# T_STorM32_motor_v24E-molex.net
KiCad netlist of a schematic drawn in EAGLE
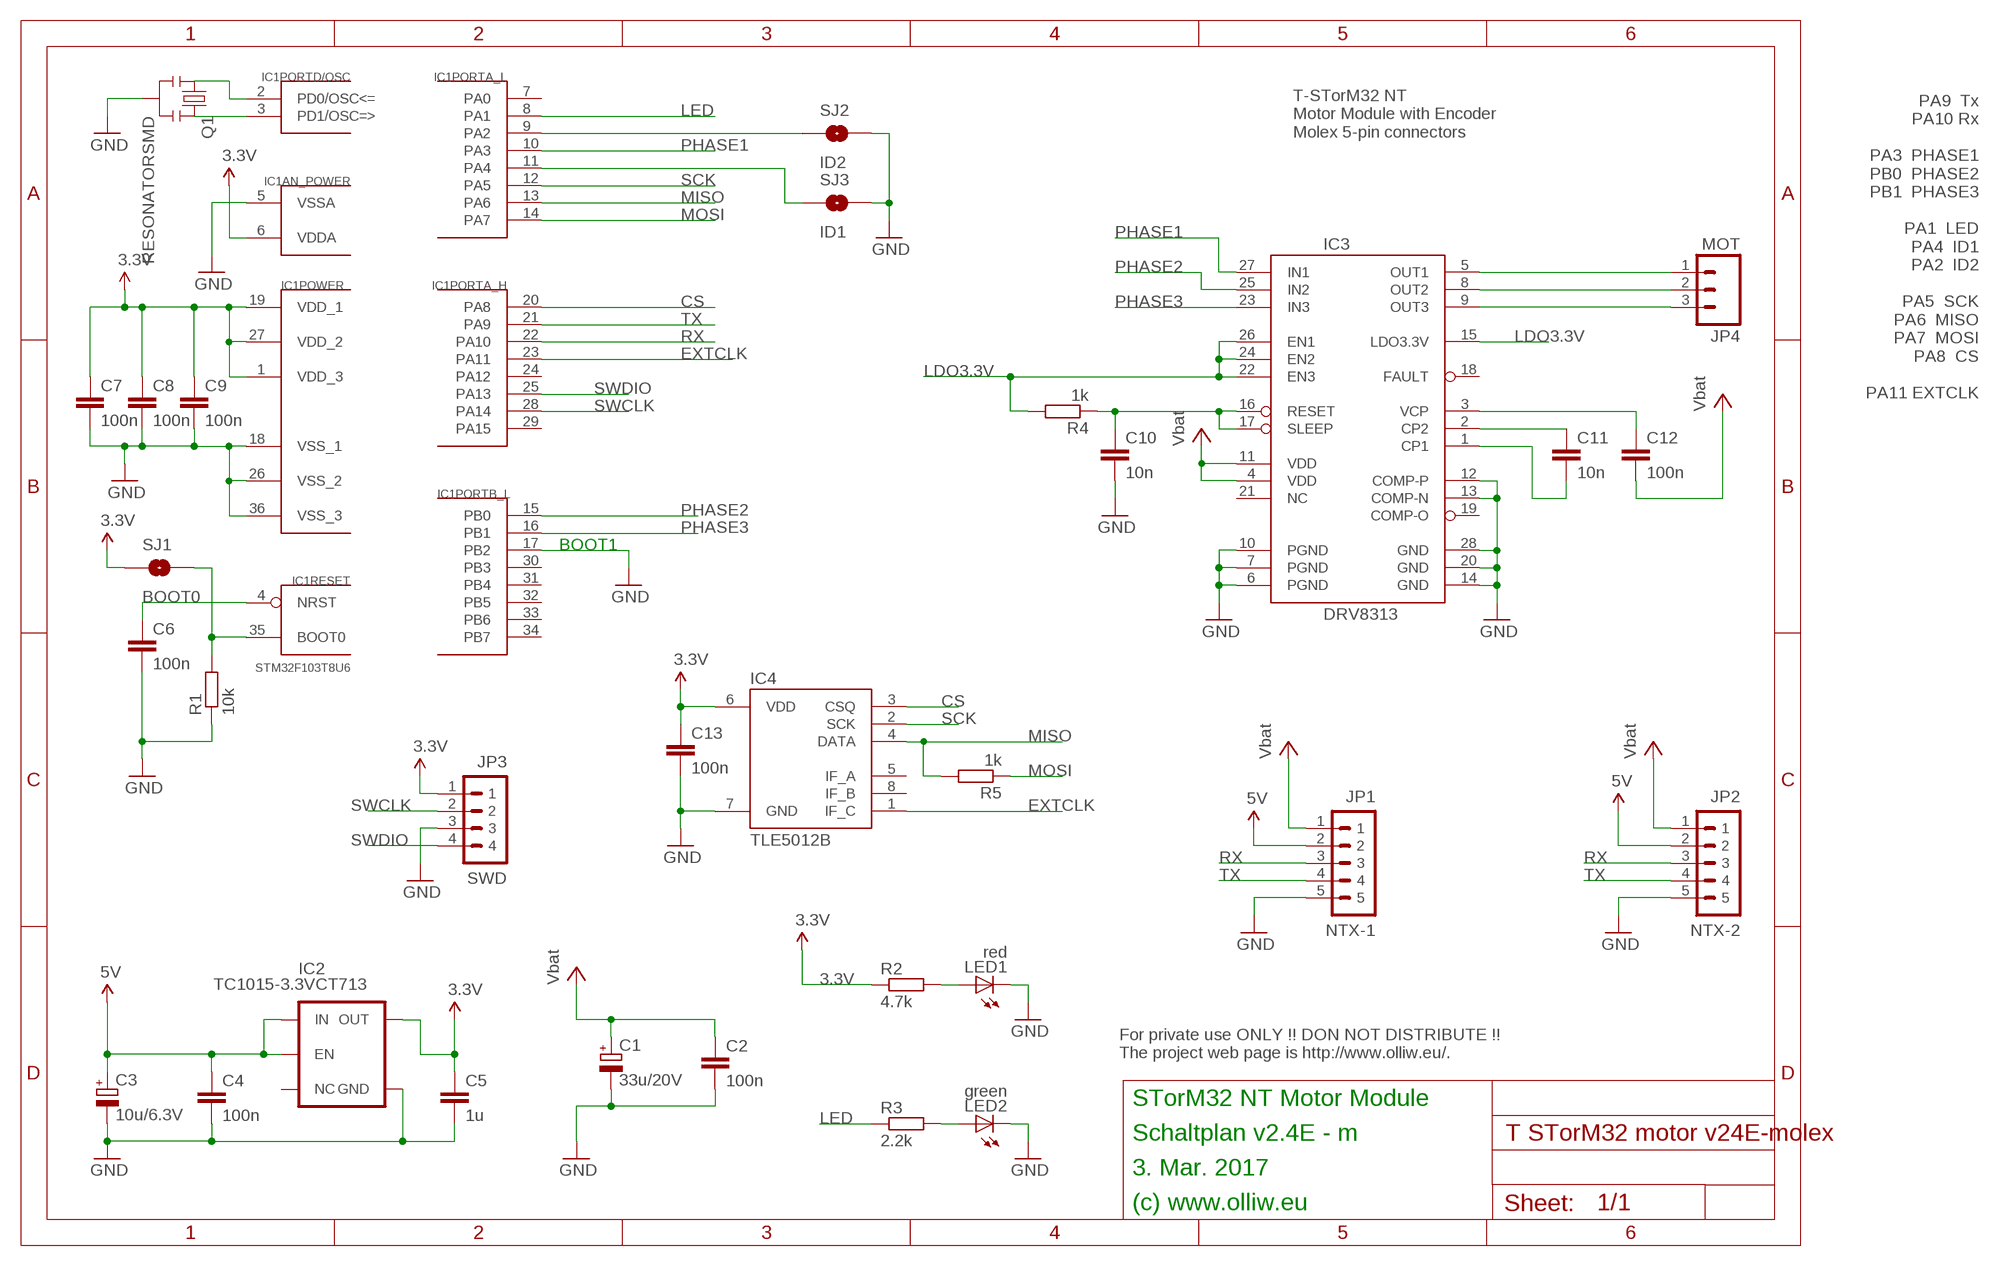
[diagram p0: schematic, sheet 1]

(export (version "E")
  (design (tool "Eeschema 10.0.6"))
  (components
    (comp (ref "C1")
      (value "33u/20V")
      (footprint "eagle-import:SMC_C")
      (libsource (lib "eagle-import") (part "CPOL-EUSMCC"))
    )
    (comp (ref "C2")
      (value "100n")
      (footprint "eagle-import:C0603")
      (libsource (lib "eagle-import") (part "C-EUC0603"))
    )
    (comp (ref "C3")
      (value "10u/6.3V")
      (footprint "eagle-import:SMC_B")
      (libsource (lib "eagle-import") (part "CPOL-EUSMCB"))
    )
    (comp (ref "C4")
      (value "100n")
      (footprint "eagle-import:C0603")
      (libsource (lib "eagle-import") (part "C-EUC0603"))
    )
    (comp (ref "C5")
      (value "1u")
      (footprint "eagle-import:C0603")
      (libsource (lib "eagle-import") (part "C-EUC0603"))
    )
    (comp (ref "C6")
      (value "100n")
      (footprint "eagle-import:C0603")
      (libsource (lib "eagle-import") (part "C-EUC0603"))
    )
    (comp (ref "C7")
      (value "100n")
      (footprint "eagle-import:C0603")
      (libsource (lib "eagle-import") (part "C-EUC0603"))
    )
    (comp (ref "C8")
      (value "100n")
      (footprint "eagle-import:C0603")
      (libsource (lib "eagle-import") (part "C-EUC0603"))
    )
    (comp (ref "C9")
      (value "100n")
      (footprint "eagle-import:C0603")
      (libsource (lib "eagle-import") (part "C-EUC0603"))
    )
    (comp (ref "C10")
      (value "10n")
      (footprint "eagle-import:C0603")
      (libsource (lib "eagle-import") (part "C-EUC0603"))
    )
    (comp (ref "C11")
      (value "10n")
      (footprint "eagle-import:C0603")
      (libsource (lib "eagle-import") (part "C-EUC0603"))
    )
    (comp (ref "C12")
      (value "100n")
      (footprint "eagle-import:C0603")
      (libsource (lib "eagle-import") (part "C-EUC0603"))
    )
    (comp (ref "C13")
      (value "100n")
      (footprint "eagle-import:C0603")
      (libsource (lib "eagle-import") (part "C-EUC0603"))
    )
    (comp (ref "IC1")
      (value "STM32F103T8U6")
      (footprint "eagle-import:VFQFPN36")
      (libsource (lib "eagle-import") (part "STM32F10XTXU6"))
    )
    (comp (ref "IC2")
      (value "TC1015-3.3VCT713")
      (footprint "eagle-import:SOT23-5")
      (libsource (lib "eagle-import") (part "V_REG_TPS76433SOT23-5"))
    )
    (comp (ref "IC3")
      (value "DRV8313")
      (footprint "eagle-import:HTSSOP28")
      (libsource (lib "eagle-import") (part "DRV8313"))
    )
    (comp (ref "IC4")
      (value "TLE5012B")
      (footprint "eagle-import:SO08")
      (libsource (lib "eagle-import") (part "TLE5012B"))
    )
    (comp (ref "JP1")
      (value "NTX-1")
      (footprint "eagle-import:MOLEX-53261-05-SMD-FLAT")
      (libsource (lib "eagle-import") (part "P5X1_1P27"))
    )
    (comp (ref "JP2")
      (value "NTX-2")
      (footprint "eagle-import:MOLEX-53261-05-SMD-FLAT")
      (libsource (lib "eagle-import") (part "P5X1_1P27"))
    )
    (comp (ref "JP3")
      (value "SWD")
      (footprint "eagle-import:4X1_1P27_OCT_BILEX")
      (libsource (lib "eagle-import") (part "P4X1_1P27-OCT_BILEX"))
    )
    (comp (ref "JP4")
      (value "MOT")
      (footprint "eagle-import:1X03")
      (libsource (lib "eagle-import") (part "M03PTH"))
    )
    (comp (ref "LED1")
      (value "red")
      (footprint "eagle-import:CHIPLED_0603")
      (libsource (lib "eagle-import") (part "LEDCHIPLED_0603"))
    )
    (comp (ref "LED2")
      (value "green")
      (footprint "eagle-import:CHIPLED_0603")
      (libsource (lib "eagle-import") (part "LEDCHIPLED_0603"))
    )
    (comp (ref "Q1")
      (value "RESONATORSMD")
      (footprint "eagle-import:RESONATOR-SMD")
      (libsource (lib "eagle-import") (part "RESONATORSMD"))
    )
    (comp (ref "R1")
      (value "10k")
      (footprint "eagle-import:R0603")
      (libsource (lib "eagle-import") (part "R-EU_R0603"))
    )
    (comp (ref "R2")
      (value "4.7k")
      (footprint "eagle-import:R0603")
      (libsource (lib "eagle-import") (part "R-EU_R0603"))
    )
    (comp (ref "R3")
      (value "2.2k")
      (footprint "eagle-import:R0603")
      (libsource (lib "eagle-import") (part "R-EU_R0603"))
    )
    (comp (ref "R4")
      (value "1k")
      (footprint "eagle-import:R0603")
      (libsource (lib "eagle-import") (part "R-EU_R0603"))
    )
    (comp (ref "R5")
      (value "1k")
      (footprint "eagle-import:R0603")
      (libsource (lib "eagle-import") (part "R-EU_R0603"))
    )
    (comp (ref "SJ1")
      (value "BOOT0")
      (footprint "eagle-import:SJ_2S-NO")
      (libsource (lib "eagle-import") (part "SOLDERJUMPERNO"))
    )
    (comp (ref "SJ2")
      (value "ID2")
      (footprint "eagle-import:SJ_2S-NO")
      (libsource (lib "eagle-import") (part "SOLDERJUMPERNO"))
    )
    (comp (ref "SJ3")
      (value "ID1")
      (footprint "eagle-import:SJ_2S-NO")
      (libsource (lib "eagle-import") (part "SOLDERJUMPERNO"))
    )
  )
  (nets
    (net (code "1") (name "/CS") (class "Default")
      (node (ref "IC1") (pin "20") (pinfunction "PA8_20") (pintype "bidirectional"))
      (node (ref "IC4") (pin "3") (pinfunction "CSQ_3") (pintype "input"))
    )
    (net (code "2") (name "/EXTCLK") (class "Default")
      (node (ref "IC1") (pin "23") (pinfunction "PA11_23") (pintype "bidirectional"))
      (node (ref "IC4") (pin "1") (pinfunction "IF_C_1") (pintype "bidirectional"))
    )
    (net (code "3") (name "/LDO3.3V") (class "Default")
      (node (ref "IC3") (pin "15") (pinfunction "LDO3.3V_15") (pintype "output"))
      (node (ref "IC3") (pin "22") (pinfunction "EN3_22") (pintype "input"))
      (node (ref "IC3") (pin "24") (pinfunction "EN2_24") (pintype "input"))
      (node (ref "IC3") (pin "26") (pinfunction "EN1_26") (pintype "input"))
      (node (ref "R4") (pin "2") (pinfunction "2_2") (pintype "passive"))
    )
    (net (code "4") (name "/LED") (class "Default")
      (node (ref "IC1") (pin "8") (pinfunction "PA1_8") (pintype "bidirectional"))
      (node (ref "R3") (pin "1") (pinfunction "1_1") (pintype "passive"))
    )
    (net (code "5") (name "/MISO") (class "Default")
      (node (ref "IC1") (pin "13") (pinfunction "PA6_13") (pintype "bidirectional"))
      (node (ref "IC4") (pin "4") (pinfunction "DATA_4") (pintype "bidirectional"))
      (node (ref "R5") (pin "2") (pinfunction "2_2") (pintype "passive"))
    )
    (net (code "6") (name "/MOSI") (class "Default")
      (node (ref "IC1") (pin "14") (pinfunction "PA7_14") (pintype "bidirectional"))
      (node (ref "R5") (pin "1") (pinfunction "1_1") (pintype "passive"))
    )
    (net (code "7") (name "/PHASE1") (class "Default")
      (node (ref "IC1") (pin "10") (pinfunction "PA3_10") (pintype "bidirectional"))
      (node (ref "IC3") (pin "27") (pinfunction "IN1_27") (pintype "input"))
    )
    (net (code "8") (name "/PHASE2") (class "Default")
      (node (ref "IC1") (pin "15") (pinfunction "PB0_15") (pintype "bidirectional"))
      (node (ref "IC3") (pin "25") (pinfunction "IN2_25") (pintype "input"))
    )
    (net (code "9") (name "/PHASE3") (class "Default")
      (node (ref "IC1") (pin "16") (pinfunction "PB1_16") (pintype "bidirectional"))
      (node (ref "IC3") (pin "23") (pinfunction "IN3_23") (pintype "input"))
    )
    (net (code "10") (name "/RX") (class "Default")
      (node (ref "IC1") (pin "22") (pinfunction "PA10_22") (pintype "bidirectional"))
      (node (ref "JP1") (pin "3") (pinfunction "3_3") (pintype "passive"))
      (node (ref "JP2") (pin "3") (pinfunction "3_3") (pintype "passive"))
    )
    (net (code "11") (name "/SCK") (class "Default")
      (node (ref "IC1") (pin "12") (pinfunction "PA5_12") (pintype "bidirectional"))
      (node (ref "IC4") (pin "2") (pinfunction "SCK_2") (pintype "input"))
    )
    (net (code "12") (name "/SWCLK") (class "Default")
      (node (ref "IC1") (pin "28") (pinfunction "PA14_28") (pintype "bidirectional"))
      (node (ref "JP3") (pin "2") (pinfunction "2_2") (pintype "passive"))
    )
    (net (code "13") (name "/SWDIO") (class "Default")
      (node (ref "IC1") (pin "25") (pinfunction "PA13_25") (pintype "bidirectional"))
      (node (ref "JP3") (pin "4") (pinfunction "4_4") (pintype "passive"))
    )
    (net (code "14") (name "/TX") (class "Default")
      (node (ref "IC1") (pin "21") (pinfunction "PA9_21") (pintype "bidirectional"))
      (node (ref "JP1") (pin "4") (pinfunction "4_4") (pintype "passive"))
      (node (ref "JP2") (pin "4") (pinfunction "4_4") (pintype "passive"))
    )
    (net (code "15") (name "3.3V") (class "Default")
      (node (ref "C13") (pin "1") (pinfunction "1_1") (pintype "passive"))
      (node (ref "C5") (pin "1") (pinfunction "1_1") (pintype "passive"))
      (node (ref "C7") (pin "1") (pinfunction "1_1") (pintype "passive"))
      (node (ref "C8") (pin "1") (pinfunction "1_1") (pintype "passive"))
      (node (ref "C9") (pin "1") (pinfunction "1_1") (pintype "passive"))
      (node (ref "IC1") (pin "1") (pinfunction "VDD_3_1") (pintype "power_in"))
      (node (ref "IC1") (pin "19") (pinfunction "VDD_1_19") (pintype "power_in"))
      (node (ref "IC1") (pin "27") (pinfunction "VDD_2_27") (pintype "power_in"))
      (node (ref "IC1") (pin "6") (pinfunction "VDDA_6") (pintype "power_in"))
      (node (ref "IC2") (pin "5") (pinfunction "OUT_5") (pintype "passive"))
      (node (ref "IC4") (pin "6") (pinfunction "VDD_6") (pintype "power_in"))
      (node (ref "JP3") (pin "1") (pinfunction "1_1") (pintype "passive"))
      (node (ref "R2") (pin "1") (pinfunction "1_1") (pintype "passive"))
      (node (ref "SJ1") (pin "1") (pinfunction "1_1") (pintype "passive"))
    )
    (net (code "16") (name "5V") (class "Default")
      (node (ref "C3") (pin "+") (pinfunction "+_+") (pintype "passive"))
      (node (ref "C4") (pin "1") (pinfunction "1_1") (pintype "passive"))
      (node (ref "IC2") (pin "1") (pinfunction "IN_1") (pintype "input"))
      (node (ref "IC2") (pin "3") (pinfunction "EN_3") (pintype "input"))
      (node (ref "JP1") (pin "2") (pinfunction "2_2") (pintype "passive"))
      (node (ref "JP2") (pin "2") (pinfunction "2_2") (pintype "passive"))
    )
    (net (code "17") (name "GND") (class "Default")
      (node (ref "C1") (pin "-") (pinfunction "-_-") (pintype "passive"))
      (node (ref "C10") (pin "2") (pinfunction "2_2") (pintype "passive"))
      (node (ref "C13") (pin "2") (pinfunction "2_2") (pintype "passive"))
      (node (ref "C2") (pin "2") (pinfunction "2_2") (pintype "passive"))
      (node (ref "C3") (pin "-") (pinfunction "-_-") (pintype "passive"))
      (node (ref "C4") (pin "2") (pinfunction "2_2") (pintype "passive"))
      (node (ref "C5") (pin "2") (pinfunction "2_2") (pintype "passive"))
      (node (ref "C6") (pin "2") (pinfunction "2_2") (pintype "passive"))
      (node (ref "C7") (pin "2") (pinfunction "2_2") (pintype "passive"))
      (node (ref "C8") (pin "2") (pinfunction "2_2") (pintype "passive"))
      (node (ref "C9") (pin "2") (pinfunction "2_2") (pintype "passive"))
      (node (ref "IC1") (pin "17") (pinfunction "PB2_17") (pintype "bidirectional"))
      (node (ref "IC1") (pin "18") (pinfunction "VSS_1_18") (pintype "power_in"))
      (node (ref "IC1") (pin "26") (pinfunction "VSS_2_26") (pintype "power_in"))
      (node (ref "IC1") (pin "36") (pinfunction "VSS_3_36") (pintype "power_in"))
      (node (ref "IC1") (pin "5") (pinfunction "VSSA_5") (pintype "power_in"))
      (node (ref "IC2") (pin "2") (pinfunction "GND_2") (pintype "input"))
      (node (ref "IC3") (pin "10") (pinfunction "PGND_10") (pintype "power_in"))
      (node (ref "IC3") (pin "12") (pinfunction "COMP-P_12") (pintype "input"))
      (node (ref "IC3") (pin "13") (pinfunction "COMP-N_13") (pintype "input"))
      (node (ref "IC3") (pin "14") (pinfunction "GND_14") (pintype "power_in"))
      (node (ref "IC3") (pin "20") (pinfunction "GND_20") (pintype "power_in"))
      (node (ref "IC3") (pin "28") (pinfunction "GND_28") (pintype "power_in"))
      (node (ref "IC3") (pin "6") (pinfunction "PGND_6") (pintype "power_in"))
      (node (ref "IC3") (pin "7") (pinfunction "PGND_7") (pintype "power_in"))
      (node (ref "IC4") (pin "7") (pinfunction "GND_7") (pintype "power_in"))
      (node (ref "JP1") (pin "5") (pinfunction "5_5") (pintype "passive"))
      (node (ref "JP2") (pin "5") (pinfunction "5_5") (pintype "passive"))
      (node (ref "JP3") (pin "3") (pinfunction "3_3") (pintype "passive"))
      (node (ref "LED1") (pin "C") (pinfunction "C_C") (pintype "passive"))
      (node (ref "LED2") (pin "C") (pinfunction "C_C") (pintype "passive"))
      (node (ref "Q1") (pin "2") (pinfunction "2_2") (pintype "passive"))
      (node (ref "R1") (pin "1") (pinfunction "1_1") (pintype "passive"))
      (node (ref "SJ2") (pin "2") (pinfunction "2_2") (pintype "passive"))
      (node (ref "SJ3") (pin "2") (pinfunction "2_2") (pintype "passive"))
    )
    (net (code "18") (name "Net-(IC1C-PA2)") (class "Default")
      (node (ref "IC1") (pin "9") (pinfunction "PA2_9") (pintype "bidirectional"))
      (node (ref "SJ2") (pin "1") (pinfunction "1_1") (pintype "passive"))
    )
    (net (code "19") (name "Net-(IC1C-PA4)") (class "Default")
      (node (ref "IC1") (pin "11") (pinfunction "PA4_11") (pintype "bidirectional"))
      (node (ref "SJ3") (pin "1") (pinfunction "1_1") (pintype "passive"))
    )
    (net (code "20") (name "Net-(IC1E-PD0{slash}OSC<=)") (class "Default")
      (node (ref "IC1") (pin "2") (pinfunction "PD0/OSC<=_2") (pintype "bidirectional"))
      (node (ref "Q1") (pin "1") (pinfunction "1_1") (pintype "passive"))
    )
    (net (code "21") (name "Net-(IC1E-PD1{slash}OSC=>)") (class "Default")
      (node (ref "IC1") (pin "3") (pinfunction "PD1/OSC=>_3") (pintype "bidirectional"))
      (node (ref "Q1") (pin "3") (pinfunction "3_3") (pintype "passive"))
    )
    (net (code "22") (name "Net-(IC1G-BOOT0)") (class "Default")
      (node (ref "IC1") (pin "35") (pinfunction "BOOT0_35") (pintype "input"))
      (node (ref "R1") (pin "2") (pinfunction "2_2") (pintype "passive"))
      (node (ref "SJ1") (pin "2") (pinfunction "2_2") (pintype "passive"))
    )
    (net (code "23") (name "Net-(IC1G-NRST)") (class "Default")
      (node (ref "C6") (pin "1") (pinfunction "1_1") (pintype "passive"))
      (node (ref "IC1") (pin "4") (pinfunction "NRST_4") (pintype "input"))
    )
    (net (code "24") (name "Net-(IC3-CP1)") (class "Default")
      (node (ref "C11") (pin "2") (pinfunction "2_2") (pintype "passive"))
      (node (ref "IC3") (pin "1") (pinfunction "CP1_1") (pintype "bidirectional"))
    )
    (net (code "25") (name "Net-(IC3-CP2)") (class "Default")
      (node (ref "C11") (pin "1") (pinfunction "1_1") (pintype "passive"))
      (node (ref "IC3") (pin "2") (pinfunction "CP2_2") (pintype "bidirectional"))
    )
    (net (code "26") (name "Net-(IC3-OUT1)") (class "Default")
      (node (ref "IC3") (pin "5") (pinfunction "OUT1_5") (pintype "output"))
      (node (ref "JP4") (pin "1") (pinfunction "1_1") (pintype "passive"))
    )
    (net (code "27") (name "Net-(IC3-OUT2)") (class "Default")
      (node (ref "IC3") (pin "8") (pinfunction "OUT2_8") (pintype "output"))
      (node (ref "JP4") (pin "2") (pinfunction "2_2") (pintype "passive"))
    )
    (net (code "28") (name "Net-(IC3-OUT3)") (class "Default")
      (node (ref "IC3") (pin "9") (pinfunction "OUT3_9") (pintype "output"))
      (node (ref "JP4") (pin "3") (pinfunction "3_3") (pintype "passive"))
    )
    (net (code "29") (name "Net-(IC3-RESET)") (class "Default")
      (node (ref "C10") (pin "1") (pinfunction "1_1") (pintype "passive"))
      (node (ref "IC3") (pin "16") (pinfunction "RESET_16") (pintype "input"))
      (node (ref "IC3") (pin "17") (pinfunction "SLEEP_17") (pintype "input"))
      (node (ref "R4") (pin "1") (pinfunction "1_1") (pintype "passive"))
    )
    (net (code "30") (name "Net-(IC3-VCP)") (class "Default")
      (node (ref "C12") (pin "1") (pinfunction "1_1") (pintype "passive"))
      (node (ref "IC3") (pin "3") (pinfunction "VCP_3") (pintype "bidirectional"))
    )
    (net (code "31") (name "Net-(LED1-PadA)") (class "Default")
      (node (ref "LED1") (pin "A") (pinfunction "A_A") (pintype "passive"))
      (node (ref "R2") (pin "2") (pinfunction "2_2") (pintype "passive"))
    )
    (net (code "32") (name "Net-(LED2-PadA)") (class "Default")
      (node (ref "LED2") (pin "A") (pinfunction "A_A") (pintype "passive"))
      (node (ref "R3") (pin "2") (pinfunction "2_2") (pintype "passive"))
    )
    (net (code "33") (name "Vbat") (class "Default")
      (node (ref "C1") (pin "+") (pinfunction "+_+") (pintype "passive"))
      (node (ref "C12") (pin "2") (pinfunction "2_2") (pintype "passive"))
      (node (ref "C2") (pin "1") (pinfunction "1_1") (pintype "passive"))
      (node (ref "IC3") (pin "11") (pinfunction "VDD_11") (pintype "power_in"))
      (node (ref "IC3") (pin "4") (pinfunction "VDD_4") (pintype "power_in"))
      (node (ref "JP1") (pin "1") (pinfunction "1_1") (pintype "passive"))
      (node (ref "JP2") (pin "1") (pinfunction "1_1") (pintype "passive"))
    )
    (net (code "34") (name "unconnected-(IC1B-PA12-Pad24)") (class "Default")
      (node (ref "IC1") (pin "24") (pinfunction "PA12_24") (pintype "bidirectional"))
    )
    (net (code "35") (name "unconnected-(IC1B-PA15-Pad29)") (class "Default")
      (node (ref "IC1") (pin "29") (pinfunction "PA15_29") (pintype "bidirectional"))
    )
    (net (code "36") (name "unconnected-(IC1C-PA0-Pad7)") (class "Default")
      (node (ref "IC1") (pin "7") (pinfunction "PA0_7") (pintype "bidirectional"))
    )
    (net (code "37") (name "unconnected-(IC1D-PB3-Pad30)") (class "Default")
      (node (ref "IC1") (pin "30") (pinfunction "PB3_30") (pintype "bidirectional"))
    )
    (net (code "38") (name "unconnected-(IC1D-PB4-Pad31)") (class "Default")
      (node (ref "IC1") (pin "31") (pinfunction "PB4_31") (pintype "bidirectional"))
    )
    (net (code "39") (name "unconnected-(IC1D-PB5-Pad32)") (class "Default")
      (node (ref "IC1") (pin "32") (pinfunction "PB5_32") (pintype "bidirectional"))
    )
    (net (code "40") (name "unconnected-(IC1D-PB6-Pad33)") (class "Default")
      (node (ref "IC1") (pin "33") (pinfunction "PB6_33") (pintype "bidirectional"))
    )
    (net (code "41") (name "unconnected-(IC1D-PB7-Pad34)") (class "Default")
      (node (ref "IC1") (pin "34") (pinfunction "PB7_34") (pintype "bidirectional"))
    )
    (net (code "42") (name "unconnected-(IC2-NC-Pad4)") (class "Default")
      (node (ref "IC2") (pin "4") (pinfunction "NC_4") (pintype "input"))
    )
    (net (code "43") (name "unconnected-(IC3-COMP-O-Pad19)") (class "Default")
      (node (ref "IC3") (pin "19") (pinfunction "COMP-O_19") (pintype "output"))
    )
    (net (code "44") (name "unconnected-(IC3-FAULT-Pad18)") (class "Default")
      (node (ref "IC3") (pin "18") (pinfunction "FAULT_18") (pintype "output"))
    )
    (net (code "45") (name "unconnected-(IC3-NC-Pad21)") (class "Default")
      (node (ref "IC3") (pin "21") (pinfunction "NC_21") (pintype "no_connect"))
    )
    (net (code "46") (name "unconnected-(IC4-IF_A-Pad5)") (class "Default")
      (node (ref "IC4") (pin "5") (pinfunction "IF_A_5") (pintype "bidirectional"))
    )
    (net (code "47") (name "unconnected-(IC4-IF_B-Pad8)") (class "Default")
      (node (ref "IC4") (pin "8") (pinfunction "IF_B_8") (pintype "output"))
    )
  )
)
